# basic_diagram.net
KiCad netlist of a schematic drawn in Altium Designer
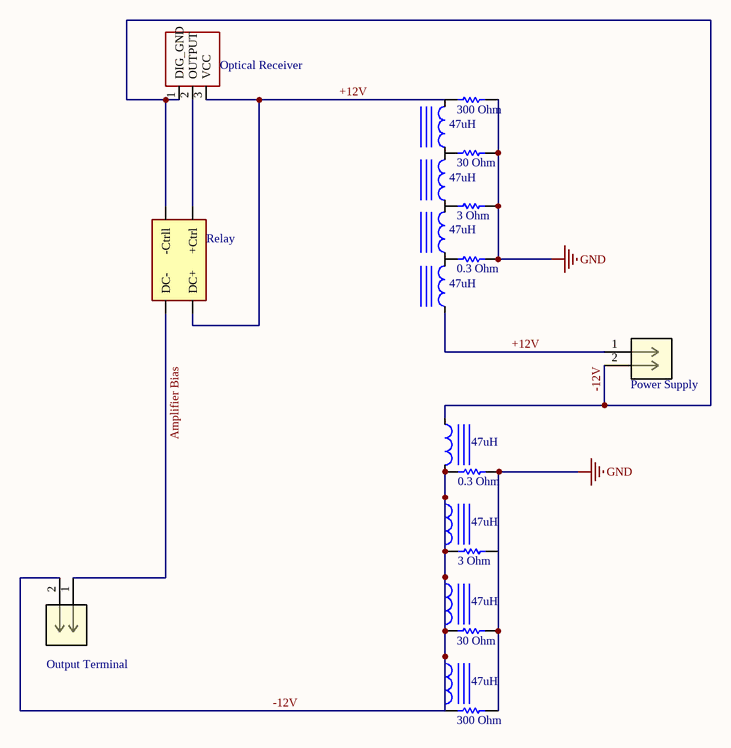
[diagram p0: basic_diagram.SchDoc]

(export (version "E")
  (design (tool "Eeschema 10.0.6"))
  (components
    (comp (ref "0.3 Ohm")
      (value "ERJ-2BQJR30X")
      (footprint "03 Ohm")
      (description "RES 0.3 OHM 5% 1/6W 0402")
      (fields (field (name "MANUFACTURER") "Panasonic") (field (name "TOLERANCE") "5%"))
      (libsource (lib "ps_schlib") (part "ERJ-2BQJR30X"))
    )
    (comp (ref "3 Ohm")
      (value "ERJ-8GEYJ3R0V")
      (footprint "3 ohm")
      (description "Res Thick Film 1206 3 Ohm 5% 1/4W -100ppm/C to 600ppm/C Molded SMD Punched Carrier T/R")
      (fields (field (name "MANUFACTURER") "Panasonic") (field (name "TOLERANCE") "5%"))
      (libsource (lib "ps_schlib") (part "ERJ-8GEYJ3R0V"))
    )
    (comp (ref "30 Ohm")
      (value "ERJ1GNF30R0C")
      (footprint "30 Ohm")
      (description "Thick Film Resistors 0201 30ohm 1% HalogenFree AEC-Q200")
      (fields (field (name "MANUFACTURER") "Panasonic") (field (name "TOLERANCE") "1%"))
      (libsource (lib "ps_schlib") (part "ERJ1GNF30R0C"))
    )
    (comp (ref "47uH")
      (value "DR127-470-R")
      (footprint "47 uH")
      (description "FIXED IND 47UH 2.95A 71.9 MOHM")
      (fields (field (name "MANUFACTURER") "Eaton Cooper") (field (name "TOLERANCE") "20%"))
      (libsource (lib "ps_schlib") (part "DR127-470-R"))
    )
    (comp (ref "300 Ohm")
      (value "ERA-2AEB301X")
      (footprint "300 Ohm")
      (fields (field (name "MANUFACTURER") "Panasonic") (field (name "TOLERANCE") "0.1%"))
      (libsource (lib "ps_schlib") (part "ERA-2AEB301X"))
    )
    (comp (ref "Optical Receiver")
      (value "IF-D95T")
      (footprint "IF-D95")
      (description "DETECTOR PHOTOLOGIC TTL/CMOS")
      (fields (field (name "MANUFACTURER") "Industrial Fiber Optics"))
      (libsource (lib "ps_schlib") (part "IF-D95T"))
    )
    (comp (ref "Output Terminal")
      (value "1054311102")
      (footprint "CONN_1054311102_MOL")
      (fields (field (name "MANUFACTURER") "Molex"))
      (libsource (lib "") (part "1054311102_1"))
    )
    (comp (ref "Power Supply")
      (value "1054311102")
      (footprint "CONN_1054311102_MOL")
      (fields (field (name "MANUFACTURER") "Molex"))
      (libsource (lib "ps_schlib") (part "1054311102"))
    )
    (comp (ref "Relay")
      (value "Solid state relay")
      (footprint "CPC1002N")
      (libsource (lib "ps_schlib") (part "CPC1002N"))
    )
  )
  (nets
    (net (code "1") (name "/+12V") (class "Default")
      (node (ref "300 Ohm") (pin "1") (pinfunction "1_1") (pintype "passive"))
      (node (ref "47uH") (pin "1") (pinfunction "1_1") (pintype "passive"))
      (node (ref "Optical Receiver") (pin "3") (pinfunction "VCC_3") (pintype "passive"))
      (node (ref "Power Supply") (pin "1") (pinfunction "1_1") (pintype "passive"))
      (node (ref "Relay") (pin "4") (pinfunction "DC+_4") (pintype "passive"))
    )
    (net (code "2") (name "/-12V") (class "Default")
      (node (ref "300 Ohm") (pin "1") (pinfunction "1_1") (pintype "passive"))
      (node (ref "47uH") (pin "1") (pinfunction "1_1") (pintype "passive"))
      (node (ref "Optical Receiver") (pin "1") (pinfunction "DIG_GND_1") (pintype "passive"))
      (node (ref "Output Terminal") (pin "2") (pinfunction "2_2") (pintype "passive"))
      (node (ref "Power Supply") (pin "2") (pinfunction "2_2") (pintype "passive"))
      (node (ref "Relay") (pin "2") (pinfunction "-Ctrll_2") (pintype "passive"))
    )
    (net (code "4") (name "/Amplifier Bias") (class "Default")
      (node (ref "Output Terminal") (pin "1") (pinfunction "1_1") (pintype "passive"))
      (node (ref "Relay") (pin "3") (pinfunction "DC-_3") (pintype "passive"))
    )
    (net (code "5") (name "GND") (class "Default")
      (node (ref "0.3 Ohm") (pin "1") (pinfunction "1_1") (pintype "passive"))
      (node (ref "0.3 Ohm") (pin "2") (pinfunction "2_2") (pintype "passive"))
      (node (ref "3 Ohm") (pin "2") (pinfunction "2_2") (pintype "passive"))
      (node (ref "30 Ohm") (pin "2") (pinfunction "2_2") (pintype "passive"))
      (node (ref "300 Ohm") (pin "2") (pinfunction "2_2") (pintype "passive"))
    )
    (net (code "6") (name "Net-(0.3 Ohm-Pad2)") (class "Default")
      (node (ref "0.3 Ohm") (pin "2") (pinfunction "2_2") (pintype "passive"))
      (node (ref "3 Ohm") (pin "1") (pinfunction "1_1") (pintype "passive"))
      (node (ref "47uH") (pin "1") (pinfunction "1_1") (pintype "passive"))
      (node (ref "47uH") (pin "2") (pinfunction "2_2") (pintype "passive"))
    )
    (net (code "7") (name "Net-(47uH-Pad1)") (class "Default")
      (node (ref "47uH") (pin "1") (pinfunction "1_1") (pintype "passive"))
      (node (ref "47uH") (pin "2") (pinfunction "2_2") (pintype "passive"))
    )
    (net (code "8") (name "Net-(Optical Receiver-OUTPUT)") (class "Default")
      (node (ref "Optical Receiver") (pin "2") (pinfunction "OUTPUT_2") (pintype "passive"))
      (node (ref "Relay") (pin "1") (pinfunction "+Ctrl_1") (pintype "passive"))
    )
    (net (code "9") (name "unconnected-(0.3 Ohm-Pad1)") (class "Default")
      (node (ref "0.3 Ohm") (pin "1") (pinfunction "1_1") (pintype "passive"))
    )
    (net (code "10") (name "unconnected-(3 Ohm-Pad1)") (class "Default")
      (node (ref "3 Ohm") (pin "1") (pinfunction "1_1") (pintype "passive"))
    )
    (net (code "11") (name "unconnected-(3 Ohm-Pad2)") (class "Default")
      (node (ref "3 Ohm") (pin "2") (pinfunction "2_2") (pintype "passive"))
    )
    (net (code "12") (name "unconnected-(30 Ohm-Pad1)") (class "Default")
      (node (ref "30 Ohm") (pin "1") (pinfunction "1_1") (pintype "passive"))
    )
    (net (code "13") (name "unconnected-(30 Ohm-Pad1)_1") (class "Default")
      (node (ref "30 Ohm") (pin "1") (pinfunction "1_1") (pintype "passive"))
    )
    (net (code "14") (name "unconnected-(47uH-Pad1)_1") (class "Default")
      (node (ref "47uH") (pin "1") (pinfunction "1_1") (pintype "passive"))
    )
    (net (code "15") (name "unconnected-(47uH-Pad1)_2") (class "Default")
      (node (ref "47uH") (pin "1") (pinfunction "1_1") (pintype "passive"))
    )
    (net (code "16") (name "unconnected-(47uH-Pad2)") (class "Default")
      (node (ref "47uH") (pin "2") (pinfunction "2_2") (pintype "passive"))
    )
    (net (code "17") (name "unconnected-(47uH-Pad2)_1") (class "Default")
      (node (ref "47uH") (pin "2") (pinfunction "2_2") (pintype "passive"))
    )
    (net (code "18") (name "unconnected-(47uH-Pad2)_2") (class "Default")
      (node (ref "47uH") (pin "2") (pinfunction "2_2") (pintype "passive"))
    )
  )
)
